# DRV8412.net
KiCad netlist of a schematic drawn in Altium Designer
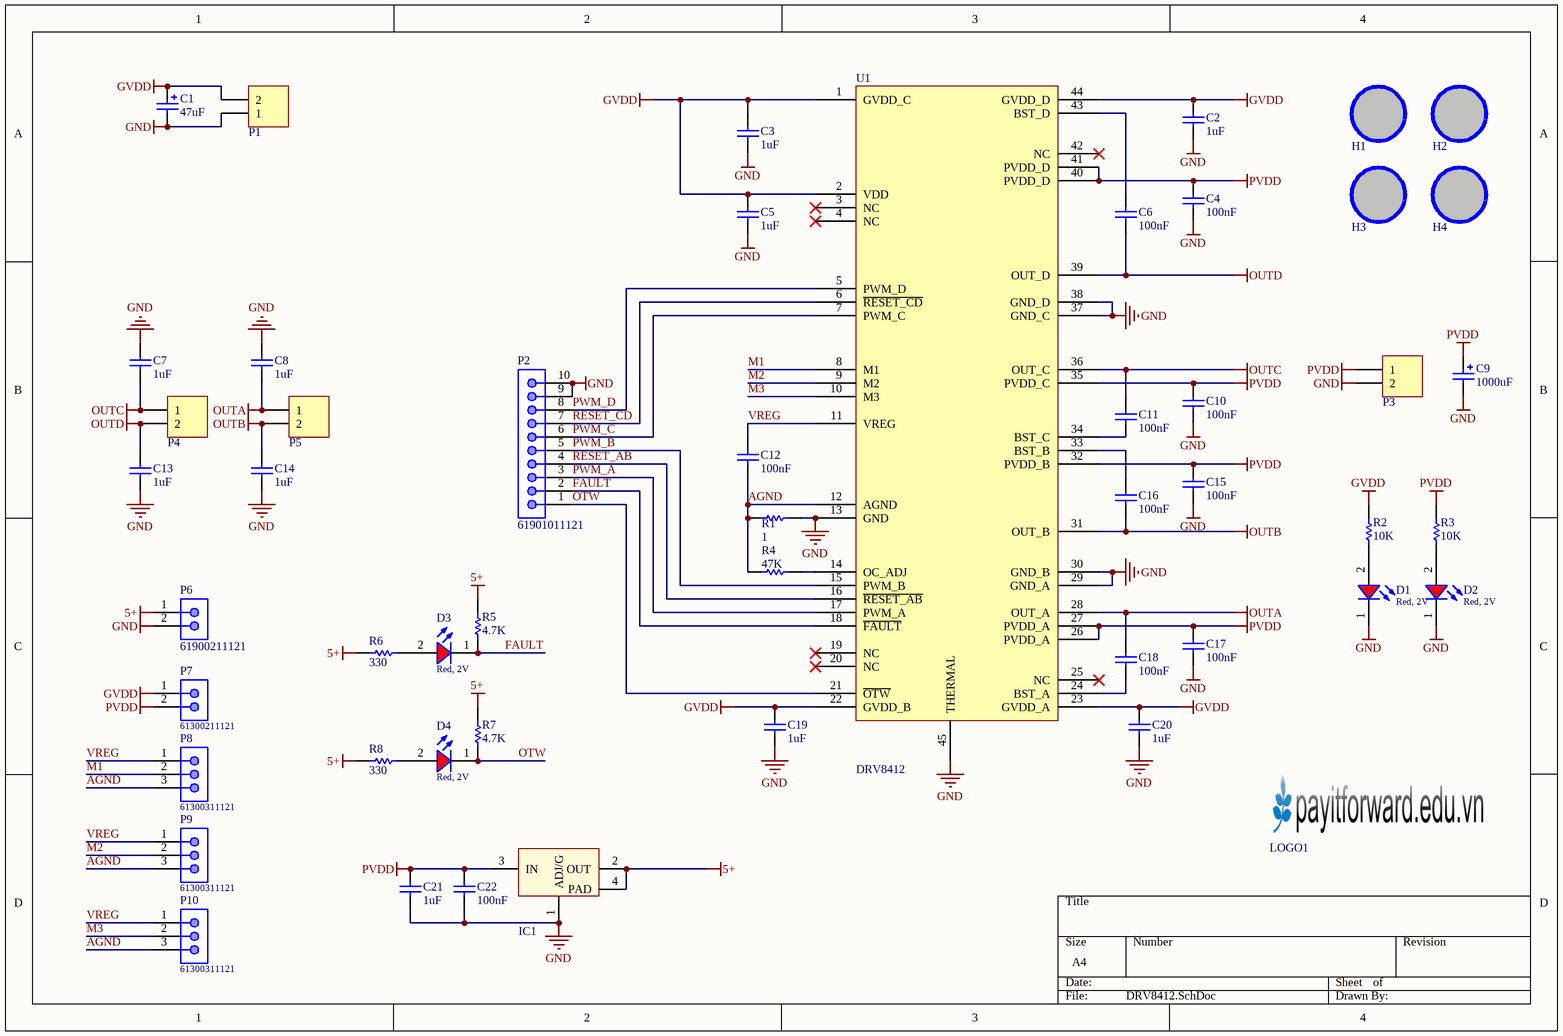
[diagram p0: DRV8412.SchDoc]

(export (version "E")
  (design (tool "Eeschema 10.0.6"))
  (components
    (comp (ref "C1")
      (value "47uF")
      (footprint "CAP ALU SIZE D")
      (description "Polarized Capacitor (Radial)")
      (fields (field (name "Comment") "Cap Pol SMD"))
      (libsource (lib "PIF_Library") (part "Cap Pol SMD"))
    )
    (comp (ref "C2")
      (value "1uF")
      (footprint "CAP-SM-0603")
      (description "Capacitor")
      (fields (field (name "Comment") "Cap Non-Pol SMD"))
      (libsource (lib "PIF_Library") (part "Cap Non-Pol SMD"))
    )
    (comp (ref "C3")
      (value "1uF")
      (footprint "CAP-SM-0603")
      (description "Capacitor")
      (fields (field (name "Comment") "Cap Non-Pol SMD"))
      (libsource (lib "PIF_Library") (part "Cap Non-Pol SMD"))
    )
    (comp (ref "C4")
      (value "100nF")
      (footprint "CAP-SM-0603")
      (description "Capacitor")
      (fields (field (name "Comment") "Cap Non-Pol SMD"))
      (libsource (lib "PIF_Library") (part "Cap Non-Pol SMD"))
    )
    (comp (ref "C5")
      (value "1uF")
      (footprint "CAP-SM-0603")
      (description "Capacitor")
      (fields (field (name "Comment") "Cap Non-Pol SMD"))
      (libsource (lib "PIF_Library") (part "Cap Non-Pol SMD"))
    )
    (comp (ref "C6")
      (value "100nF")
      (footprint "CAP-SM-0603")
      (description "Capacitor")
      (fields (field (name "Comment") "Cap Non-Pol SMD"))
      (libsource (lib "PIF_Library") (part "Cap Non-Pol SMD"))
    )
    (comp (ref "C7")
      (value "1uF")
      (footprint "CAP-SM-0805")
      (description "Capacitor")
      (fields (field (name "Comment") "Cap Non-Pol SMD"))
      (libsource (lib "PIF_Library") (part "Cap Non-Pol SMD"))
    )
    (comp (ref "C8")
      (value "1uF")
      (footprint "CAP-SM-0805")
      (description "Capacitor")
      (fields (field (name "Comment") "Cap Non-Pol SMD"))
      (libsource (lib "PIF_Library") (part "Cap Non-Pol SMD"))
    )
    (comp (ref "C9")
      (value "1000uF")
      (footprint "CP2/5")
      (description "Polarized Capacitor (Radial)")
      (fields (field (name "Comment") "Cap Pol"))
      (libsource (lib "PIF_Library") (part "Cap Pol"))
    )
    (comp (ref "C10")
      (value "100nF")
      (footprint "CAP-SM-0603")
      (description "Capacitor")
      (fields (field (name "Comment") "Cap Non-Pol SMD"))
      (libsource (lib "PIF_Library") (part "Cap Non-Pol SMD"))
    )
    (comp (ref "C11")
      (value "100nF")
      (footprint "CAP-SM-0603")
      (description "Capacitor")
      (fields (field (name "Comment") "Cap Non-Pol SMD"))
      (libsource (lib "PIF_Library") (part "Cap Non-Pol SMD"))
    )
    (comp (ref "C12")
      (value "100nF")
      (footprint "CAP-SM-0603")
      (description "Capacitor")
      (fields (field (name "Comment") "Cap Non-Pol SMD"))
      (libsource (lib "PIF_Library") (part "Cap Non-Pol SMD"))
    )
    (comp (ref "C13")
      (value "1uF")
      (footprint "CAP-SM-0805")
      (description "Capacitor")
      (fields (field (name "Comment") "Cap Non-Pol SMD"))
      (libsource (lib "PIF_Library") (part "Cap Non-Pol SMD"))
    )
    (comp (ref "C14")
      (value "1uF")
      (footprint "CAP-SM-0805")
      (description "Capacitor")
      (fields (field (name "Comment") "Cap Non-Pol SMD"))
      (libsource (lib "PIF_Library") (part "Cap Non-Pol SMD"))
    )
    (comp (ref "C15")
      (value "100nF")
      (footprint "CAP-SM-0603")
      (description "Capacitor")
      (fields (field (name "Comment") "Cap Non-Pol SMD"))
      (libsource (lib "PIF_Library") (part "Cap Non-Pol SMD"))
    )
    (comp (ref "C16")
      (value "100nF")
      (footprint "CAP-SM-0603")
      (description "Capacitor")
      (fields (field (name "Comment") "Cap Non-Pol SMD"))
      (libsource (lib "PIF_Library") (part "Cap Non-Pol SMD"))
    )
    (comp (ref "C17")
      (value "100nF")
      (footprint "CAP-SM-0603")
      (description "Capacitor")
      (fields (field (name "Comment") "Cap Non-Pol SMD"))
      (libsource (lib "PIF_Library") (part "Cap Non-Pol SMD"))
    )
    (comp (ref "C18")
      (value "100nF")
      (footprint "CAP-SM-0603")
      (description "Capacitor")
      (fields (field (name "Comment") "Cap Non-Pol SMD"))
      (libsource (lib "PIF_Library") (part "Cap Non-Pol SMD"))
    )
    (comp (ref "C19")
      (value "1uF")
      (footprint "CAP-SM-0603")
      (description "Capacitor")
      (fields (field (name "Comment") "Cap Non-Pol SMD"))
      (libsource (lib "PIF_Library") (part "Cap Non-Pol SMD"))
    )
    (comp (ref "C20")
      (value "1uF")
      (footprint "CAP-SM-0603")
      (description "Capacitor")
      (fields (field (name "Comment") "Cap Non-Pol SMD"))
      (libsource (lib "PIF_Library") (part "Cap Non-Pol SMD"))
    )
    (comp (ref "C21")
      (value "1uF")
      (footprint "CAP-SM-0603")
      (description "Capacitor")
      (fields (field (name "Comment") "Cap Non-Pol SMD"))
      (libsource (lib "PIF_Library") (part "Cap Non-Pol SMD"))
    )
    (comp (ref "C22")
      (value "100nF")
      (footprint "CAP-SM-0603")
      (description "Capacitor")
      (fields (field (name "Comment") "Cap Non-Pol SMD"))
      (libsource (lib "PIF_Library") (part "Cap Non-Pol SMD"))
    )
    (comp (ref "D1")
      (value "Red, 2V")
      (footprint "WL-SMCW_0603_H=0.7mm")
      (description "WL-SMCW SMT Mono-color Chip LED Waterclear, size 0603, Red, 2V, 140deg")
      (fields (field (name "PART NUMBER") "150060RS75000") (field (name "PUBLISHER") "Wurth Elektronik"))
      (libsource (lib "Altium_WL-SMCW (rev20a)") (part "150060RS75000"))
    )
    (comp (ref "D2")
      (value "Red, 2V")
      (footprint "WL-SMCW_0603_H=0.7mm")
      (description "WL-SMCW SMT Mono-color Chip LED Waterclear, size 0603, Red, 2V, 140deg")
      (fields (field (name "PART NUMBER") "150060RS75000") (field (name "PUBLISHER") "Wurth Elektronik"))
      (libsource (lib "Altium_WL-SMCW (rev20a)") (part "150060RS75000"))
    )
    (comp (ref "D3")
      (value "Red, 2V")
      (footprint "WL-SMCW_0603_H=0.7mm")
      (description "WL-SMCW SMT Mono-color Chip LED Waterclear, size 0603, Red, 2V, 140deg")
      (fields (field (name "PART NUMBER") "150060RS75000") (field (name "PUBLISHER") "Wurth Elektronik"))
      (libsource (lib "Altium_WL-SMCW (rev20a)") (part "150060RS75000"))
    )
    (comp (ref "D4")
      (value "Red, 2V")
      (footprint "WL-SMCW_0603_H=0.7mm")
      (description "WL-SMCW SMT Mono-color Chip LED Waterclear, size 0603, Red, 2V, 140deg")
      (fields (field (name "PART NUMBER") "150060RS75000") (field (name "PUBLISHER") "Wurth Elektronik"))
      (libsource (lib "Altium_WL-SMCW (rev20a)") (part "150060RS75000"))
    )
    (comp (ref "H1")
      (value "Hole")
      (footprint "LO KHOAN 3MM")
      (description "Hole 3mm")
      (libsource (lib "PIF_Library") (part "Hole"))
    )
    (comp (ref "H2")
      (value "Hole")
      (footprint "LO KHOAN 3MM")
      (description "Hole 3mm")
      (libsource (lib "PIF_Library") (part "Hole"))
    )
    (comp (ref "H3")
      (value "Hole")
      (footprint "LO KHOAN 3MM")
      (description "Hole 3mm")
      (libsource (lib "PIF_Library") (part "Hole"))
    )
    (comp (ref "H4")
      (value "Hole")
      (footprint "LO KHOAN 3MM")
      (description "Hole 3mm")
      (libsource (lib "PIF_Library") (part "Hole"))
    )
    (comp (ref "IC1")
      (value "LM1117")
      (footprint "SOT223-4N")
      (description "Available in 1.8V, 2.5V, 2.85V, 3.3V, 5V, and  Adjustable Versions")
      (libsource (lib "PIF_Library") (part "LM1117"))
    )
    (comp (ref "LOGO1")
      (value "LOGO PIF")
      (footprint "PIF LOGO SMALL TOP")
      (libsource (lib "PIF_Library") (part "LOGO PIF"))
    )
    (comp (ref "P1")
      (value "Domino 2")
      (footprint "DOMINO 2- 5mm")
      (description "Domino, 2-Pin")
      (fields (field (name "PUBLISHER") "Altium Limited"))
      (libsource (lib "") (part "Domino 2_1"))
    )
    (comp (ref "P2")
      (value "61901011121")
      (footprint "61901011121")
      (description "WR-WTB THT Male Vertical Locking Header, pitch 2.54mm, 10p")
      (fields (field (name "PUBLISHER") "Wurth Elektronik"))
      (libsource (lib "653008114822_Altium_WR-WTB_rev20a") (part "61901011121"))
    )
    (comp (ref "P3")
      (value "Domino 2")
      (footprint "DOMINO 2- 5mm")
      (description "Domino, 2-Pin")
      (fields (field (name "PUBLISHER") "Altium Limited"))
      (libsource (lib "PIF_Library") (part "Domino 2"))
    )
    (comp (ref "P4")
      (value "Domino 2")
      (footprint "DOMINO 2- 5mm")
      (description "Domino, 2-Pin")
      (fields (field (name "PUBLISHER") "Altium Limited"))
      (libsource (lib "PIF_Library") (part "Domino 2"))
    )
    (comp (ref "P5")
      (value "Domino 2")
      (footprint "DOMINO 2- 5mm")
      (description "Domino, 2-Pin")
      (fields (field (name "PUBLISHER") "Altium Limited"))
      (libsource (lib "PIF_Library") (part "Domino 2"))
    )
    (comp (ref "P6")
      (value "61900211121")
      (footprint "61900211121")
      (description "WR-WTB THT Male Vertical Locking Header, pitch 2.54mm, 2p")
      (fields (field (name "PUBLISHER") "Wurth Elektronik"))
      (libsource (lib "653008114822_Altium_WR-WTB_rev20a") (part "61900211121"))
    )
    (comp (ref "P7")
      (value "61300211121")
      (footprint "61300211121")
      (description "WR-PHD Pin Header, THT, pitch 2.54mm, Single Row, Vertical, 2p")
      (fields (field (name "MANUFACTURER") "Wurth Elektronik"))
      (libsource (lib "Altium_WR-PHD (rev20a)") (part "61300211121"))
    )
    (comp (ref "P8")
      (value "61300311121")
      (footprint "61300311121")
      (description "WR-PHD Pin Header, THT, pitch 2.54mm, Single Row, Vertical, 3p")
      (fields (field (name "MANUFACTURER") "Wurth Elektronik"))
      (libsource (lib "Altium_WR-PHD (rev20a)") (part "61300311121"))
    )
    (comp (ref "P9")
      (value "61300311121")
      (footprint "61300311121")
      (description "WR-PHD Pin Header, THT, pitch 2.54mm, Single Row, Vertical, 3p")
      (fields (field (name "MANUFACTURER") "Wurth Elektronik"))
      (libsource (lib "Altium_WR-PHD (rev20a)") (part "61300311121"))
    )
    (comp (ref "P10")
      (value "61300311121")
      (footprint "61300311121")
      (description "WR-PHD Pin Header, THT, pitch 2.54mm, Single Row, Vertical, 3p")
      (fields (field (name "MANUFACTURER") "Wurth Elektronik"))
      (libsource (lib "Altium_WR-PHD (rev20a)") (part "61300311121"))
    )
    (comp (ref "R1")
      (value "1")
      (footprint "RES-SM-0603")
      (description "Resistor")
      (fields (field (name "Comment") "RESISTOR SMD"))
      (libsource (lib "PIF_Library") (part "RESISTOR SMD"))
    )
    (comp (ref "R2")
      (value "10K")
      (footprint "RES-SM-0603")
      (description "Resistor")
      (fields (field (name "Comment") "RESISTOR SMD"))
      (libsource (lib "PIF_Library") (part "RESISTOR SMD"))
    )
    (comp (ref "R3")
      (value "10K")
      (footprint "RES-SM-0603")
      (description "Resistor")
      (fields (field (name "Comment") "RESISTOR SMD"))
      (libsource (lib "PIF_Library") (part "RESISTOR SMD"))
    )
    (comp (ref "R4")
      (value "47K")
      (footprint "RES-SM-0603")
      (description "Resistor")
      (fields (field (name "Comment") "RESISTOR SMD"))
      (libsource (lib "PIF_Library") (part "RESISTOR SMD"))
    )
    (comp (ref "R5")
      (value "4.7K")
      (footprint "RES-SM-0603")
      (description "Resistor")
      (fields (field (name "Comment") "RESISTOR SMD"))
      (libsource (lib "PIF_Library") (part "RESISTOR SMD"))
    )
    (comp (ref "R6")
      (value "330")
      (footprint "RES-SM-0603")
      (description "Resistor")
      (fields (field (name "Comment") "RESISTOR SMD"))
      (libsource (lib "PIF_Library") (part "RESISTOR SMD"))
    )
    (comp (ref "R7")
      (value "4.7K")
      (footprint "RES-SM-0603")
      (description "Resistor")
      (fields (field (name "Comment") "RESISTOR SMD"))
      (libsource (lib "PIF_Library") (part "RESISTOR SMD"))
    )
    (comp (ref "R8")
      (value "330")
      (footprint "RES-SM-0603")
      (description "Resistor")
      (fields (field (name "Comment") "RESISTOR SMD"))
      (libsource (lib "PIF_Library") (part "RESISTOR SMD"))
    )
    (comp (ref "U1")
      (value "DRV8412")
      (footprint "TSOP64P810X150_HS-45N")
      (fields (field (name "MANUFACTURER") "Texas Instruments"))
      (libsource (lib "MiclsLib") (part "DRV8412"))
    )
  )
  (nets
    (net (code "1") (name "/AGND") (class "Default")
      (node (ref "C12") (pin "1") (pinfunction "1_1") (pintype "passive"))
      (node (ref "P10") (pin "3") (pinfunction "3_3") (pintype "passive"))
      (node (ref "P8") (pin "3") (pinfunction "3_3") (pintype "passive"))
      (node (ref "P9") (pin "3") (pinfunction "3_3") (pintype "passive"))
      (node (ref "R1") (pin "1") (pinfunction "1_1") (pintype "passive"))
      (node (ref "R4") (pin "1") (pinfunction "1_1") (pintype "passive"))
      (node (ref "U1") (pin "12") (pinfunction "AGND_12") (pintype "passive"))
    )
    (net (code "2") (name "/FAULT") (class "Default")
      (node (ref "D3") (pin "1") (pinfunction "K_1") (pintype "passive"))
      (node (ref "P2") (pin "2") (pinfunction "2_2") (pintype "passive"))
      (node (ref "R5") (pin "1") (pinfunction "1_1") (pintype "passive"))
      (node (ref "U1") (pin "18") (pinfunction "~{FAULT}_18") (pintype "passive"))
    )
    (net (code "3") (name "/M1") (class "Default")
      (node (ref "P8") (pin "2") (pinfunction "2_2") (pintype "passive"))
      (node (ref "U1") (pin "8") (pinfunction "M1_8") (pintype "passive"))
    )
    (net (code "4") (name "/M2") (class "Default")
      (node (ref "P9") (pin "2") (pinfunction "2_2") (pintype "passive"))
      (node (ref "U1") (pin "9") (pinfunction "M2_9") (pintype "passive"))
    )
    (net (code "5") (name "/M3") (class "Default")
      (node (ref "P10") (pin "2") (pinfunction "2_2") (pintype "passive"))
      (node (ref "U1") (pin "10") (pinfunction "M3_10") (pintype "passive"))
    )
    (net (code "6") (name "/OTW") (class "Default")
      (node (ref "D4") (pin "1") (pinfunction "K_1") (pintype "passive"))
      (node (ref "P2") (pin "1") (pinfunction "1_1") (pintype "passive"))
      (node (ref "R7") (pin "1") (pinfunction "1_1") (pintype "passive"))
      (node (ref "U1") (pin "21") (pinfunction "~{OTW}_21") (pintype "passive"))
    )
    (net (code "7") (name "/PWM_A") (class "Default")
      (node (ref "P2") (pin "3") (pinfunction "3_3") (pintype "passive"))
      (node (ref "U1") (pin "17") (pinfunction "PWM_A_17") (pintype "passive"))
    )
    (net (code "8") (name "/PWM_B") (class "Default")
      (node (ref "P2") (pin "5") (pinfunction "5_5") (pintype "passive"))
      (node (ref "U1") (pin "15") (pinfunction "PWM_B_15") (pintype "passive"))
    )
    (net (code "9") (name "/PWM_C") (class "Default")
      (node (ref "P2") (pin "6") (pinfunction "6_6") (pintype "passive"))
      (node (ref "U1") (pin "7") (pinfunction "PWM_C_7") (pintype "passive"))
    )
    (net (code "10") (name "/PWM_D") (class "Default")
      (node (ref "P2") (pin "8") (pinfunction "8_8") (pintype "passive"))
      (node (ref "U1") (pin "5") (pinfunction "PWM_D_5") (pintype "passive"))
    )
    (net (code "11") (name "/RESET_AB") (class "Default")
      (node (ref "P2") (pin "4") (pinfunction "4_4") (pintype "passive"))
      (node (ref "U1") (pin "16") (pinfunction "~{RESET_AB}_16") (pintype "passive"))
    )
    (net (code "12") (name "/RESET_CD") (class "Default")
      (node (ref "P2") (pin "7") (pinfunction "7_7") (pintype "passive"))
      (node (ref "U1") (pin "6") (pinfunction "~{RESET_CD}_6") (pintype "passive"))
    )
    (net (code "13") (name "/VREG") (class "Default")
      (node (ref "C12") (pin "2") (pinfunction "2_2") (pintype "passive"))
      (node (ref "P10") (pin "1") (pinfunction "1_1") (pintype "passive"))
      (node (ref "P8") (pin "1") (pinfunction "1_1") (pintype "passive"))
      (node (ref "P9") (pin "1") (pinfunction "1_1") (pintype "passive"))
      (node (ref "U1") (pin "11") (pinfunction "VREG_11") (pintype "passive"))
    )
    (net (code "14") (name "5+") (class "Default")
      (node (ref "IC1") (pin "2") (pinfunction "OUT_2") (pintype "passive"))
      (node (ref "IC1") (pin "4") (pinfunction "PAD_4") (pintype "passive"))
      (node (ref "P6") (pin "1") (pinfunction "1_1") (pintype "passive"))
      (node (ref "R5") (pin "2") (pinfunction "2_2") (pintype "passive"))
      (node (ref "R6") (pin "2") (pinfunction "2_2") (pintype "passive"))
      (node (ref "R7") (pin "2") (pinfunction "2_2") (pintype "passive"))
      (node (ref "R8") (pin "2") (pinfunction "2_2") (pintype "passive"))
    )
    (net (code "15") (name "GND") (class "Default")
      (node (ref "C1") (pin "2") (pinfunction "2_2") (pintype "passive"))
      (node (ref "C10") (pin "1") (pinfunction "1_1") (pintype "passive"))
      (node (ref "C13") (pin "1") (pinfunction "1_1") (pintype "passive"))
      (node (ref "C14") (pin "1") (pinfunction "1_1") (pintype "passive"))
      (node (ref "C15") (pin "1") (pinfunction "1_1") (pintype "passive"))
      (node (ref "C17") (pin "1") (pinfunction "1_1") (pintype "passive"))
      (node (ref "C19") (pin "1") (pinfunction "1_1") (pintype "passive"))
      (node (ref "C2") (pin "1") (pinfunction "1_1") (pintype "passive"))
      (node (ref "C20") (pin "1") (pinfunction "1_1") (pintype "passive"))
      (node (ref "C21") (pin "1") (pinfunction "1_1") (pintype "passive"))
      (node (ref "C22") (pin "1") (pinfunction "1_1") (pintype "passive"))
      (node (ref "C3") (pin "1") (pinfunction "1_1") (pintype "passive"))
      (node (ref "C4") (pin "1") (pinfunction "1_1") (pintype "passive"))
      (node (ref "C5") (pin "1") (pinfunction "1_1") (pintype "passive"))
      (node (ref "C7") (pin "2") (pinfunction "2_2") (pintype "passive"))
      (node (ref "C8") (pin "2") (pinfunction "2_2") (pintype "passive"))
      (node (ref "C9") (pin "2") (pinfunction "2_2") (pintype "passive"))
      (node (ref "D1") (pin "1") (pinfunction "K_1") (pintype "passive"))
      (node (ref "D2") (pin "1") (pinfunction "K_1") (pintype "passive"))
      (node (ref "IC1") (pin "1") (pinfunction "ADJ/G_1") (pintype "passive"))
      (node (ref "P1") (pin "1") (pinfunction "1_1") (pintype "passive"))
      (node (ref "P2") (pin "10") (pinfunction "10_10") (pintype "passive"))
      (node (ref "P2") (pin "9") (pinfunction "9_9") (pintype "passive"))
      (node (ref "P3") (pin "2") (pinfunction "2_2") (pintype "passive"))
      (node (ref "P6") (pin "2") (pinfunction "2_2") (pintype "passive"))
      (node (ref "R1") (pin "2") (pinfunction "2_2") (pintype "passive"))
      (node (ref "U1") (pin "13") (pinfunction "GND_13") (pintype "passive"))
      (node (ref "U1") (pin "29") (pinfunction "GND_A_29") (pintype "passive"))
      (node (ref "U1") (pin "30") (pinfunction "GND_B_30") (pintype "passive"))
      (node (ref "U1") (pin "37") (pinfunction "GND_C_37") (pintype "passive"))
      (node (ref "U1") (pin "38") (pinfunction "GND_D_38") (pintype "passive"))
      (node (ref "U1") (pin "45") (pinfunction "THERMAL_45") (pintype "passive"))
    )
    (net (code "16") (name "GVDD") (class "Default")
      (node (ref "C1") (pin "1") (pinfunction "1_1") (pintype "passive"))
      (node (ref "C19") (pin "2") (pinfunction "2_2") (pintype "passive"))
      (node (ref "C2") (pin "2") (pinfunction "2_2") (pintype "passive"))
      (node (ref "C20") (pin "2") (pinfunction "2_2") (pintype "passive"))
      (node (ref "C3") (pin "2") (pinfunction "2_2") (pintype "passive"))
      (node (ref "C5") (pin "2") (pinfunction "2_2") (pintype "passive"))
      (node (ref "P1") (pin "2") (pinfunction "2_2") (pintype "passive"))
      (node (ref "P7") (pin "1") (pinfunction "1_1") (pintype "passive"))
      (node (ref "R2") (pin "1") (pinfunction "1_1") (pintype "passive"))
      (node (ref "U1") (pin "1") (pinfunction "GVDD_C_1") (pintype "passive"))
      (node (ref "U1") (pin "2") (pinfunction "VDD_2") (pintype "passive"))
      (node (ref "U1") (pin "22") (pinfunction "GVDD_B_22") (pintype "passive"))
      (node (ref "U1") (pin "23") (pinfunction "GVDD_A_23") (pintype "passive"))
      (node (ref "U1") (pin "44") (pinfunction "GVDD_D_44") (pintype "passive"))
    )
    (net (code "17") (name "Net-(D1-A)") (class "Default")
      (node (ref "D1") (pin "2") (pinfunction "A_2") (pintype "passive"))
      (node (ref "R2") (pin "2") (pinfunction "2_2") (pintype "passive"))
    )
    (net (code "18") (name "Net-(D2-A)") (class "Default")
      (node (ref "D2") (pin "2") (pinfunction "A_2") (pintype "passive"))
      (node (ref "R3") (pin "2") (pinfunction "2_2") (pintype "passive"))
    )
    (net (code "19") (name "Net-(D3-A)") (class "Default")
      (node (ref "D3") (pin "2") (pinfunction "A_2") (pintype "passive"))
      (node (ref "R6") (pin "1") (pinfunction "1_1") (pintype "passive"))
    )
    (net (code "20") (name "Net-(D4-A)") (class "Default")
      (node (ref "D4") (pin "2") (pinfunction "A_2") (pintype "passive"))
      (node (ref "R8") (pin "1") (pinfunction "1_1") (pintype "passive"))
    )
    (net (code "21") (name "Net-(U1-BST_A)") (class "Default")
      (node (ref "C18") (pin "1") (pinfunction "1_1") (pintype "passive"))
      (node (ref "U1") (pin "24") (pinfunction "BST_A_24") (pintype "passive"))
    )
    (net (code "22") (name "Net-(U1-BST_B)") (class "Default")
      (node (ref "C16") (pin "2") (pinfunction "2_2") (pintype "passive"))
      (node (ref "U1") (pin "33") (pinfunction "BST_B_33") (pintype "passive"))
    )
    (net (code "23") (name "Net-(U1-BST_C)") (class "Default")
      (node (ref "C11") (pin "1") (pinfunction "1_1") (pintype "passive"))
      (node (ref "U1") (pin "34") (pinfunction "BST_C_34") (pintype "passive"))
    )
    (net (code "24") (name "Net-(U1-BST_D)") (class "Default")
      (node (ref "C6") (pin "2") (pinfunction "2_2") (pintype "passive"))
      (node (ref "U1") (pin "43") (pinfunction "BST_D_43") (pintype "passive"))
    )
    (net (code "25") (name "Net-(U1-OC_ADJ)") (class "Default")
      (node (ref "R4") (pin "2") (pinfunction "2_2") (pintype "passive"))
      (node (ref "U1") (pin "14") (pinfunction "OC_ADJ_14") (pintype "passive"))
    )
    (net (code "26") (name "OUTA") (class "Default")
      (node (ref "C18") (pin "2") (pinfunction "2_2") (pintype "passive"))
      (node (ref "C8") (pin "1") (pinfunction "1_1") (pintype "passive"))
      (node (ref "P5") (pin "1") (pinfunction "1_1") (pintype "passive"))
      (node (ref "U1") (pin "28") (pinfunction "OUT_A_28") (pintype "passive"))
    )
    (net (code "27") (name "OUTB") (class "Default")
      (node (ref "C14") (pin "2") (pinfunction "2_2") (pintype "passive"))
      (node (ref "C16") (pin "1") (pinfunction "1_1") (pintype "passive"))
      (node (ref "P5") (pin "2") (pinfunction "2_2") (pintype "passive"))
      (node (ref "U1") (pin "31") (pinfunction "OUT_B_31") (pintype "passive"))
    )
    (net (code "28") (name "OUTC") (class "Default")
      (node (ref "C11") (pin "2") (pinfunction "2_2") (pintype "passive"))
      (node (ref "C7") (pin "1") (pinfunction "1_1") (pintype "passive"))
      (node (ref "P4") (pin "1") (pinfunction "1_1") (pintype "passive"))
      (node (ref "U1") (pin "36") (pinfunction "OUT_C_36") (pintype "passive"))
    )
    (net (code "29") (name "OUTD") (class "Default")
      (node (ref "C13") (pin "2") (pinfunction "2_2") (pintype "passive"))
      (node (ref "C6") (pin "1") (pinfunction "1_1") (pintype "passive"))
      (node (ref "P4") (pin "2") (pinfunction "2_2") (pintype "passive"))
      (node (ref "U1") (pin "39") (pinfunction "OUT_D_39") (pintype "passive"))
    )
    (net (code "30") (name "PVDD") (class "Default")
      (node (ref "C10") (pin "2") (pinfunction "2_2") (pintype "passive"))
      (node (ref "C15") (pin "2") (pinfunction "2_2") (pintype "passive"))
      (node (ref "C17") (pin "2") (pinfunction "2_2") (pintype "passive"))
      (node (ref "C21") (pin "2") (pinfunction "2_2") (pintype "passive"))
      (node (ref "C22") (pin "2") (pinfunction "2_2") (pintype "passive"))
      (node (ref "C4") (pin "2") (pinfunction "2_2") (pintype "passive"))
      (node (ref "C9") (pin "1") (pinfunction "1_1") (pintype "passive"))
      (node (ref "IC1") (pin "3") (pinfunction "IN_3") (pintype "passive"))
      (node (ref "P3") (pin "1") (pinfunction "1_1") (pintype "passive"))
      (node (ref "P7") (pin "2") (pinfunction "2_2") (pintype "passive"))
      (node (ref "R3") (pin "1") (pinfunction "1_1") (pintype "passive"))
      (node (ref "U1") (pin "26") (pinfunction "PVDD_A_26") (pintype "passive"))
      (node (ref "U1") (pin "27") (pinfunction "PVDD_A_27") (pintype "passive"))
      (node (ref "U1") (pin "32") (pinfunction "PVDD_B_32") (pintype "passive"))
      (node (ref "U1") (pin "35") (pinfunction "PVDD_C_35") (pintype "passive"))
      (node (ref "U1") (pin "40") (pinfunction "PVDD_D_40") (pintype "passive"))
      (node (ref "U1") (pin "41") (pinfunction "PVDD_D_41") (pintype "passive"))
    )
    (net (code "31") (name "unconnected-(H1-Pad1)") (class "Default")
      (node (ref "H1") (pin "1") (pinfunction "1_1") (pintype "passive"))
    )
    (net (code "32") (name "unconnected-(H2-Pad1)") (class "Default")
      (node (ref "H2") (pin "1") (pinfunction "1_1") (pintype "passive"))
    )
    (net (code "33") (name "unconnected-(H3-Pad1)") (class "Default")
      (node (ref "H3") (pin "1") (pinfunction "1_1") (pintype "passive"))
    )
    (net (code "34") (name "unconnected-(H4-Pad1)") (class "Default")
      (node (ref "H4") (pin "1") (pinfunction "1_1") (pintype "passive"))
    )
    (net (code "35") (name "unconnected-(U1-NC-Pad3)") (class "Default")
      (node (ref "U1") (pin "3") (pinfunction "NC_3") (pintype "passive+no_connect"))
    )
    (net (code "36") (name "unconnected-(U1-NC-Pad4)") (class "Default")
      (node (ref "U1") (pin "4") (pinfunction "NC_4") (pintype "passive+no_connect"))
    )
    (net (code "37") (name "unconnected-(U1-NC-Pad19)") (class "Default")
      (node (ref "U1") (pin "19") (pinfunction "NC_19") (pintype "passive+no_connect"))
    )
    (net (code "38") (name "unconnected-(U1-NC-Pad20)") (class "Default")
      (node (ref "U1") (pin "20") (pinfunction "NC_20") (pintype "passive+no_connect"))
    )
    (net (code "39") (name "unconnected-(U1-NC-Pad25)") (class "Default")
      (node (ref "U1") (pin "25") (pinfunction "NC_25") (pintype "passive+no_connect"))
    )
    (net (code "40") (name "unconnected-(U1-NC-Pad42)") (class "Default")
      (node (ref "U1") (pin "42") (pinfunction "NC_42") (pintype "passive+no_connect"))
    )
  )
)
